# esp32c3phils.net
KiCad netlist of a schematic drawn in Altium Designer
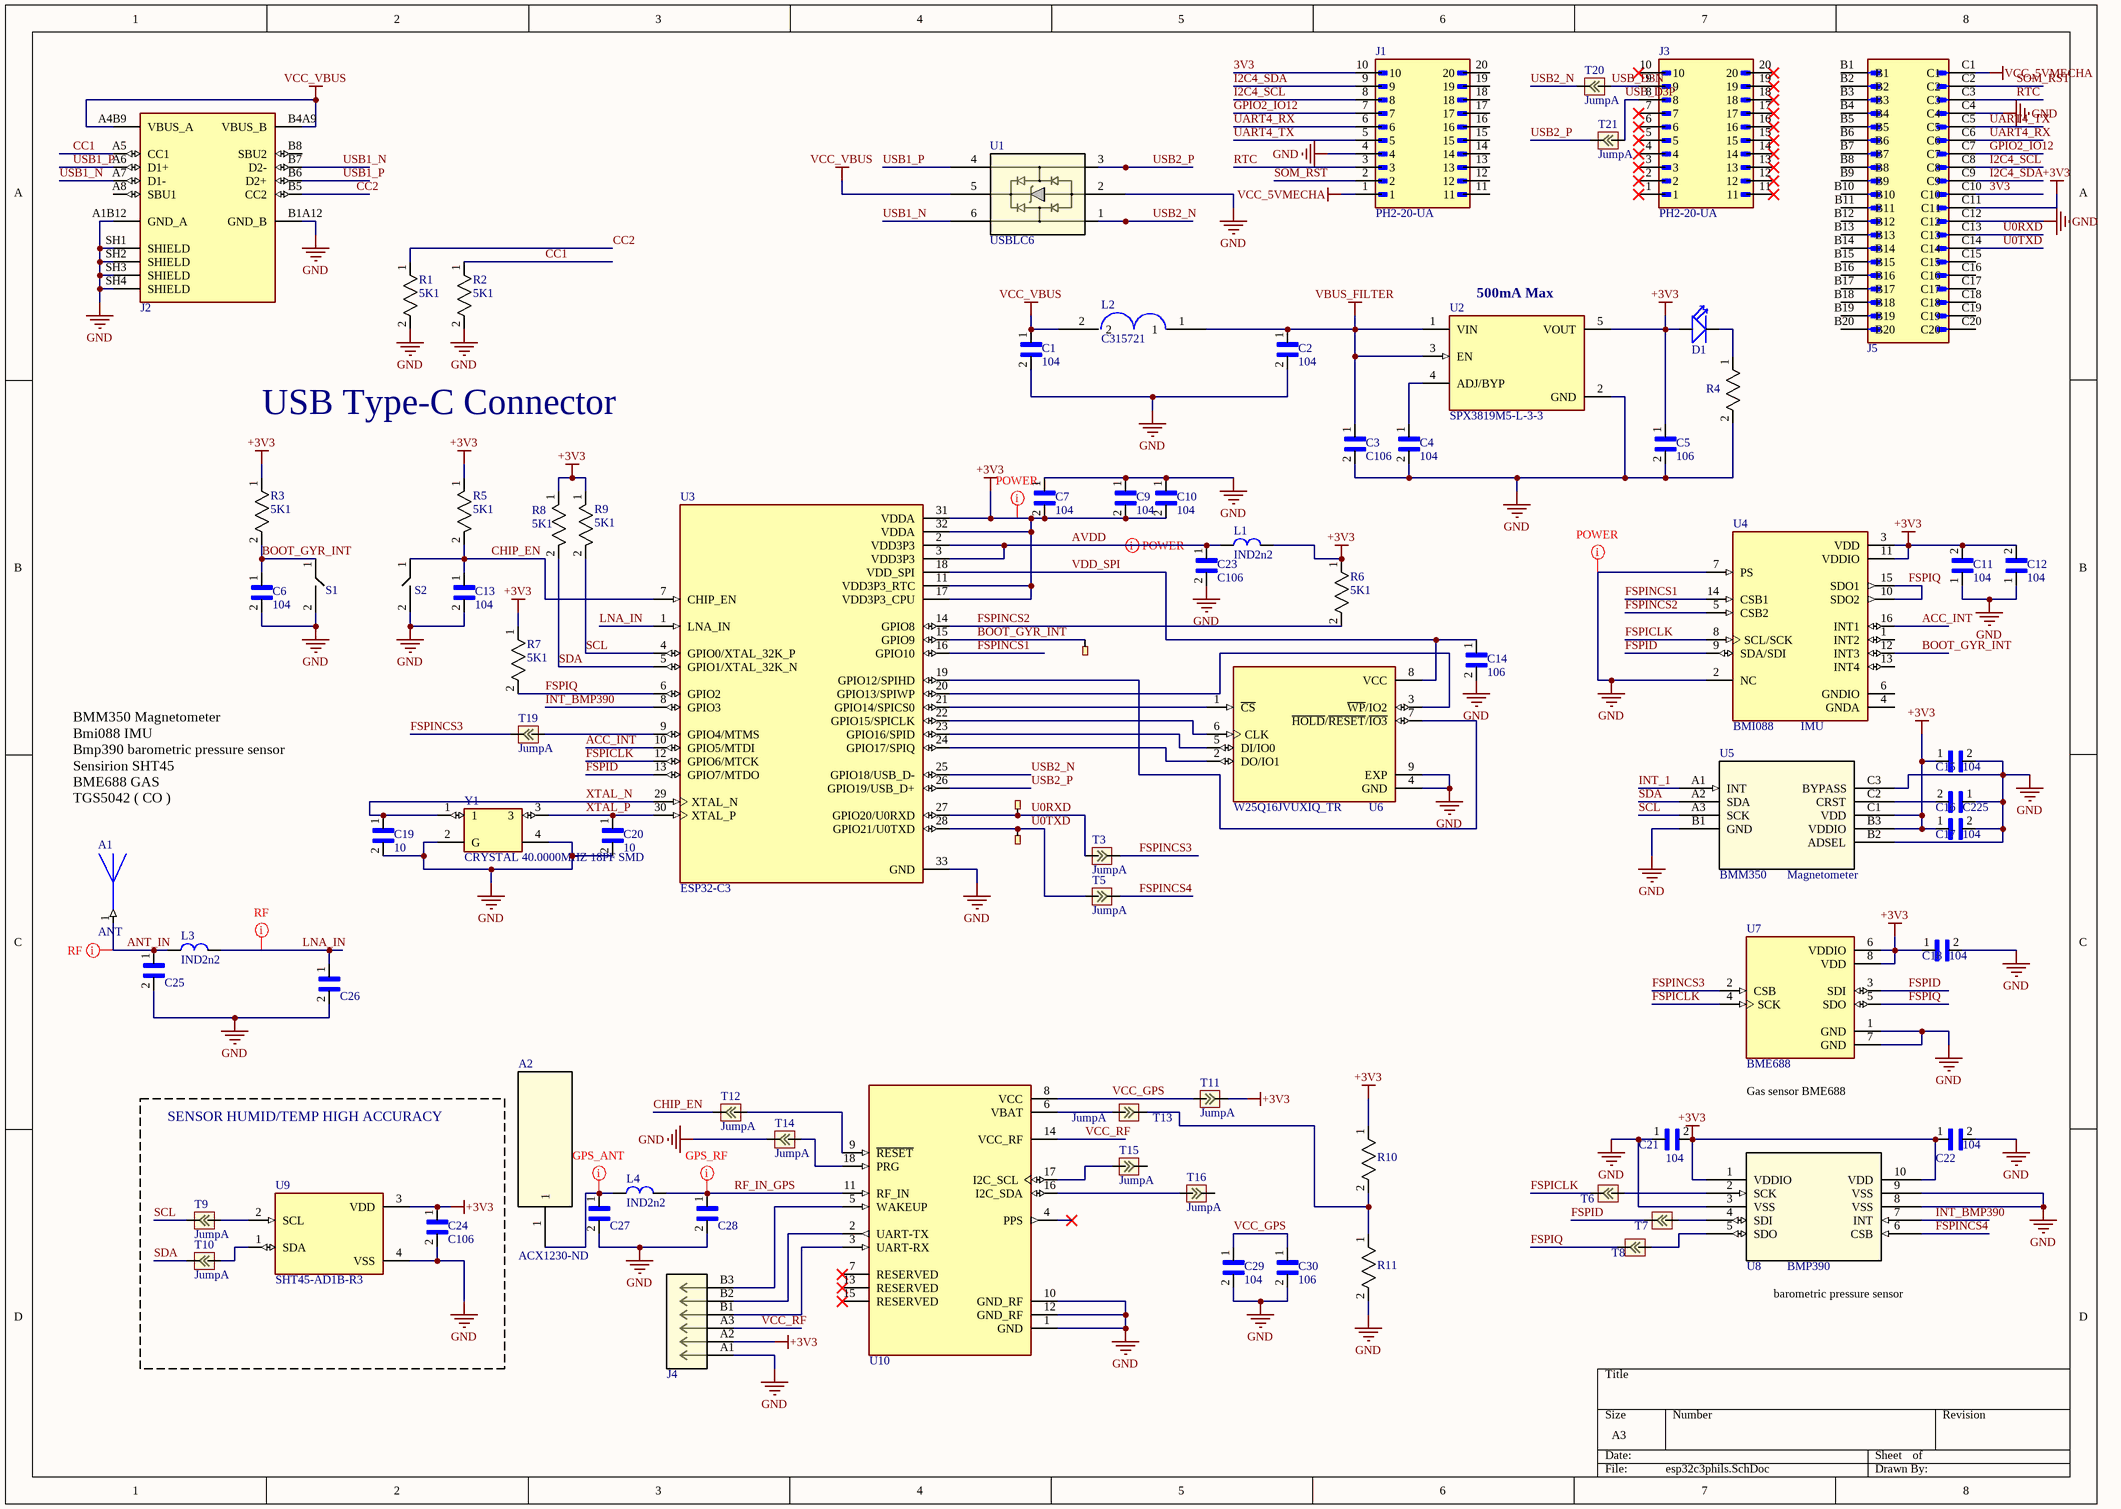
[diagram p0: esp32c3phils.SchDoc]

(export (version "E")
  (design (tool "Eeschema 10.0.6"))
  (components
    (comp (ref "A1")
      (value "ANT")
      (footprint "XDCR_AMCA31-2R450G-S1F-T3")
      (description "Chip Dielectric Antenna; 1dBi; 2450MHz; T/R ¦ Abracon AMCA31-2R450G-S1F-T3")
      (fields (field (name "MANUFACTURER") "Abracon") (field (name "MANUFACTURER PART NUMBER") "C3283994"))
      (libsource (lib "imx8mnano") (part "AMCA31-2R450G-S1F-T3"))
    )
    (comp (ref "A2")
      (value "SMA_VERTICAL")
      (footprint "SMA_VERTICAL")
      (description "connector, rf coaxial, sma str jack for p.c.board, 4 legs, .050 center cont, 50 ohm")
      (fields
        (field (name "MANUFACTURER") "Amphenol Connex")
        (field (name "MANUFACTURER PART NUMBER") "C3174425")
        (field (name "SUPPLIER PART NUMBER 1") "ACX1230-ND")
      )
      (libsource (lib "imx8mnano") (part "SMA_VERTICAL"))
    )
    (comp (ref "C1")
      (value "104")
      (footprint "CAPC1005X55N2")
      (description "Multilayer Ceramic Capacitor, 0.1 uF, 16 V, ï¿½ 10%, X7R, 0402 [1005 Metric]")
      (fields
        (field (name "MANUFACTURER") "Yageo")
        (field (name "MANUFACTURER PART NUMBER") "CC0402KRX7R7BB104")
      )
      (libsource (lib "imx8mnano") (part "CC0402KRX7R7BB104"))
    )
    (comp (ref "C2")
      (value "104")
      (footprint "CAPC1005X55N2")
      (description "Multilayer Ceramic Capacitor, 0.1 uF, 16 V, ï¿½ 10%, X7R, 0402 [1005 Metric]")
      (fields
        (field (name "MANUFACTURER") "Yageo")
        (field (name "MANUFACTURER PART NUMBER") "CC0402KRX7R7BB104")
      )
      (libsource (lib "imx8mnano") (part "CC0402KRX7R7BB104"))
    )
    (comp (ref "C3")
      (value "C106")
      (footprint "RC0402")
      (description "Multilayer Ceramic Chip Capacitor 0402 Size 10uF 10V X5R ±20% Tolerance SMD T/R")
      (fields
        (field (name "MANUFACTURER") "Kyocera AVX")
        (field (name "MANUFACTURER PART NUMBER") "C2167902")
      )
      (libsource (lib "imx8mnano") (part "0402ZD106MAT2A"))
    )
    (comp (ref "C4")
      (value "104")
      (footprint "CAPC1005X55N2")
      (description "Multilayer Ceramic Capacitor, 0.1 uF, 16 V, ï¿½ 10%, X7R, 0402 [1005 Metric]")
      (fields
        (field (name "MANUFACTURER") "Yageo")
        (field (name "MANUFACTURER PART NUMBER") "CC0402KRX7R7BB104")
      )
      (libsource (lib "imx8mnano") (part "CC0402KRX7R7BB104"))
    )
    (comp (ref "C5")
      (value "106")
      (footprint "RC0402")
      (description "Multilayer Ceramic Chip Capacitor 0402 Size 10uF 10V X5R ±20% Tolerance SMD T/R")
      (fields
        (field (name "MANUFACTURER") "Kyocera AVX")
        (field (name "MANUFACTURER PART NUMBER") "C2167902")
      )
      (libsource (lib "imx8mnano") (part "0402ZD106MAT2A"))
    )
    (comp (ref "C6")
      (value "104")
      (footprint "CAPC1005X55N2")
      (description "Multilayer Ceramic Capacitor, 0.1 uF, 16 V, ï¿½ 10%, X7R, 0402 [1005 Metric]")
      (fields
        (field (name "MANUFACTURER") "Yageo")
        (field (name "MANUFACTURER PART NUMBER") "CC0402KRX7R7BB104")
      )
      (libsource (lib "imx8mnano") (part "CC0402KRX7R7BB104"))
    )
    (comp (ref "C7")
      (value "104")
      (footprint "CAPC1005X55N2")
      (description "Multilayer Ceramic Capacitor, 0.1 uF, 16 V, ï¿½ 10%, X7R, 0402 [1005 Metric]")
      (fields
        (field (name "MANUFACTURER") "Yageo")
        (field (name "MANUFACTURER PART NUMBER") "CC0402KRX7R7BB104")
      )
      (libsource (lib "imx8mnano") (part "CC0402KRX7R7BB104"))
    )
    (comp (ref "C9")
      (value "104")
      (footprint "CAPC1005X55N2")
      (description "Multilayer Ceramic Capacitor, 0.1 uF, 16 V, ï¿½ 10%, X7R, 0402 [1005 Metric]")
      (fields
        (field (name "MANUFACTURER") "Yageo")
        (field (name "MANUFACTURER PART NUMBER") "CC0402KRX7R7BB104")
      )
      (libsource (lib "imx8mnano") (part "CC0402KRX7R7BB104"))
    )
    (comp (ref "C10")
      (value "104")
      (footprint "CAPC1005X55N2")
      (description "Multilayer Ceramic Capacitor, 0.1 uF, 16 V, ï¿½ 10%, X7R, 0402 [1005 Metric]")
      (fields
        (field (name "MANUFACTURER") "Yageo")
        (field (name "MANUFACTURER PART NUMBER") "CC0402KRX7R7BB104")
      )
      (libsource (lib "imx8mnano") (part "CC0402KRX7R7BB104"))
    )
    (comp (ref "C11")
      (value "104")
      (footprint "CAPC1005X55N2")
      (description "Multilayer Ceramic Capacitor, 0.1 uF, 16 V, ï¿½ 10%, X7R, 0402 [1005 Metric]")
      (fields
        (field (name "MANUFACTURER") "Yageo")
        (field (name "MANUFACTURER PART NUMBER") "CC0402KRX7R7BB104")
      )
      (libsource (lib "") (part "CC0402KRX7R7BB104_1"))
    )
    (comp (ref "C12")
      (value "104")
      (footprint "CAPC1005X55N2")
      (description "Multilayer Ceramic Capacitor, 0.1 uF, 16 V, ï¿½ 10%, X7R, 0402 [1005 Metric]")
      (fields
        (field (name "MANUFACTURER") "Yageo")
        (field (name "MANUFACTURER PART NUMBER") "CC0402KRX7R7BB104")
      )
      (libsource (lib "") (part "CC0402KRX7R7BB104_1"))
    )
    (comp (ref "C13")
      (value "104")
      (footprint "CAPC1005X55N2")
      (description "Multilayer Ceramic Capacitor, 0.1 uF, 16 V, ï¿½ 10%, X7R, 0402 [1005 Metric]")
      (fields
        (field (name "MANUFACTURER") "Yageo")
        (field (name "MANUFACTURER PART NUMBER") "CC0402KRX7R7BB104")
      )
      (libsource (lib "") (part "CC0402KRX7R7BB104_3"))
    )
    (comp (ref "C14")
      (value "106")
      (footprint "RC0402")
      (description "Multilayer Ceramic Chip Capacitor 0402 Size 10uF 10V X5R ±20% Tolerance SMD T/R")
      (fields
        (field (name "MANUFACTURER") "Kyocera AVX")
        (field (name "MANUFACTURER PART NUMBER") "C2167902")
      )
      (libsource (lib "imx8mnano") (part "0402ZD106MAT2A"))
    )
    (comp (ref "C15")
      (value "104")
      (footprint "CAPC1005X55N2")
      (description "Multilayer Ceramic Capacitor, 0.1 uF, 16 V, ï¿½ 10%, X7R, 0402 [1005 Metric]")
      (fields
        (field (name "MANUFACTURER") "Yageo")
        (field (name "MANUFACTURER PART NUMBER") "CC0402KRX7R7BB104")
      )
      (libsource (lib "") (part "CC0402KRX7R7BB104_2"))
    )
    (comp (ref "C16")
      (value "C225")
      (footprint "RC0402X")
      (description "Multilayer Ceramic Capacitor, 2.2 uF, 6.3 V, ï¿½ 20%, X5R, 0402 [1005 Metric]")
      (fields
        (field (name "MANUFACTURER") "Samsung")
        (field (name "MANUFACTURER PART NUMBER") "CL05A225MQ5NNNC")
      )
      (libsource (lib "imx8mnano") (part "C225"))
    )
    (comp (ref "C17")
      (value "104")
      (footprint "CAPC1005X55N2")
      (description "Multilayer Ceramic Capacitor, 0.1 uF, 16 V, ï¿½ 10%, X7R, 0402 [1005 Metric]")
      (fields
        (field (name "MANUFACTURER") "Yageo")
        (field (name "MANUFACTURER PART NUMBER") "CC0402KRX7R7BB104")
      )
      (libsource (lib "") (part "CC0402KRX7R7BB104_2"))
    )
    (comp (ref "C18")
      (value "104")
      (footprint "CAPC1005X55N2")
      (description "Multilayer Ceramic Capacitor, 0.1 uF, 16 V, ï¿½ 10%, X7R, 0402 [1005 Metric]")
      (fields
        (field (name "MANUFACTURER") "Yageo")
        (field (name "MANUFACTURER PART NUMBER") "CC0402KRX7R7BB104")
      )
      (libsource (lib "") (part "CC0402KRX7R7BB104_2"))
    )
    (comp (ref "C19")
      (value "10")
      (footprint "RC0402")
      (description "0402 10 pF 50 V ±5 % Tolerance NP0 SMT Multilayer Ceramic Capacitor")
      (fields
        (field (name "MANUFACTURER") "Yageo")
        (field (name "MANUFACTURER PART NUMBER") "CC0402JRNPO9BN100")
      )
      (libsource (lib "imx8mnano") (part "C10"))
    )
    (comp (ref "C20")
      (value "10")
      (footprint "RC0402")
      (description "0402 10 pF 50 V ±5 % Tolerance NP0 SMT Multilayer Ceramic Capacitor")
      (fields
        (field (name "MANUFACTURER") "Yageo")
        (field (name "MANUFACTURER PART NUMBER") "CC0402JRNPO9BN100")
      )
      (libsource (lib "imx8mnano") (part "C10"))
    )
    (comp (ref "C21")
      (value "104")
      (footprint "CAPC1005X55N2")
      (description "Multilayer Ceramic Capacitor, 0.1 uF, 16 V, ï¿½ 10%, X7R, 0402 [1005 Metric]")
      (fields
        (field (name "MANUFACTURER") "Yageo")
        (field (name "MANUFACTURER PART NUMBER") "CC0402KRX7R7BB104")
      )
      (libsource (lib "") (part "CC0402KRX7R7BB104_2"))
    )
    (comp (ref "C22")
      (value "104")
      (footprint "CAPC1005X55N2")
      (description "Multilayer Ceramic Capacitor, 0.1 uF, 16 V, ï¿½ 10%, X7R, 0402 [1005 Metric]")
      (fields
        (field (name "MANUFACTURER") "Yageo")
        (field (name "MANUFACTURER PART NUMBER") "CC0402KRX7R7BB104")
      )
      (libsource (lib "") (part "CC0402KRX7R7BB104_2"))
    )
    (comp (ref "C23")
      (value "C106")
      (footprint "RC0402")
      (description "Multilayer Ceramic Chip Capacitor 0402 Size 10uF 10V X5R ±20% Tolerance SMD T/R")
      (fields
        (field (name "MANUFACTURER") "Kyocera AVX")
        (field (name "MANUFACTURER PART NUMBER") "C2167902")
      )
      (libsource (lib "imx8mnano") (part "0402ZD106MAT2A"))
    )
    (comp (ref "C24")
      (value "C106")
      (footprint "RC0402")
      (description "Multilayer Ceramic Chip Capacitor 0402 Size 10uF 10V X5R ±20% Tolerance SMD T/R")
      (fields
        (field (name "MANUFACTURER") "Kyocera AVX")
        (field (name "MANUFACTURER PART NUMBER") "C2167902")
      )
      (libsource (lib "imx8mnano") (part "0402ZD106MAT2A"))
    )
    (comp (ref "C25")
      (value "GJM1555C1H3R3BB01D")
      (footprint "RC0402")
      (description "Multilayer Ceramic Capacitors MLCC - SMD/SMT 0402 3.3pF 50Volts C0G +/-0.1pF")
      (fields (field (name "MANUFACTURER") "Murata") (field (name "MANUFACTURER PART NUMBER") "C76906"))
      (libsource (lib "imx8mnano") (part "3.3PF0402LCSC"))
    )
    (comp (ref "C26")
      (value "GJM1555C1H3R3BB01D")
      (footprint "RC0402")
      (description "Multilayer Ceramic Capacitors MLCC - SMD/SMT 0402 3.3pF 50Volts C0G +/-0.1pF")
      (fields (field (name "MANUFACTURER") "Murata") (field (name "MANUFACTURER PART NUMBER") "C76906"))
      (libsource (lib "imx8mnano") (part "3.3PF0402LCSC"))
    )
    (comp (ref "C27")
      (value "GJM1555C1H3R3BB01D")
      (footprint "RC0402")
      (description "Multilayer Ceramic Capacitors MLCC - SMD/SMT 0402 3.3pF 50Volts C0G +/-0.1pF")
      (fields (field (name "MANUFACTURER") "Murata") (field (name "MANUFACTURER PART NUMBER") "C76906"))
      (libsource (lib "imx8mnano") (part "3.3PF0402LCSC"))
    )
    (comp (ref "C28")
      (value "GJM1555C1H3R3BB01D")
      (footprint "RC0402")
      (description "Multilayer Ceramic Capacitors MLCC - SMD/SMT 0402 3.3pF 50Volts C0G +/-0.1pF")
      (fields (field (name "MANUFACTURER") "Murata") (field (name "MANUFACTURER PART NUMBER") "C76906"))
      (libsource (lib "imx8mnano") (part "3.3PF0402LCSC"))
    )
    (comp (ref "C29")
      (value "104")
      (footprint "CAPC1005X55N2")
      (description "Multilayer Ceramic Capacitor, 0.1 uF, 16 V, ï¿½ 10%, X7R, 0402 [1005 Metric]")
      (fields
        (field (name "MANUFACTURER") "Yageo")
        (field (name "MANUFACTURER PART NUMBER") "CC0402KRX7R7BB104")
      )
      (libsource (lib "imx8mnano") (part "CC0402KRX7R7BB104"))
    )
    (comp (ref "C30")
      (value "106")
      (footprint "RC0402")
      (description "Multilayer Ceramic Chip Capacitor 0402 Size 10uF 10V X5R ±20% Tolerance SMD T/R")
      (fields
        (field (name "MANUFACTURER") "Kyocera AVX")
        (field (name "MANUFACTURER PART NUMBER") "C2167902")
      )
      (libsource (lib "imx8mnano") (part "0402ZD106MAT2A"))
    )
    (comp (ref "D1")
      (value "LED")
      (footprint "LEDM1608X80")
      (description "Single Color LED, Ultra Bright Orange, Water Clear, 1.1mm")
      (fields
        (field (name "MANUFACTURER") "Vishay Lite-On")
        (field (name "MANUFACTURER PART NUMBER") "C157740")
      )
      (libsource (lib "imx8mnano") (part "LTST-C190KFKT"))
    )
    (comp (ref "J1")
      (value "PH2-20-UA")
      (footprint "HEADERPAD_20_80MIL")
      (fields (field (name "MF") "{'manufacturer': u'Adam Tech'}"))
      (libsource (lib "imx8mnano") (part "PH2-20-UA"))
    )
    (comp (ref "J2")
      (value "GSB1C411111DS1HR")
      (footprint "AMPHENOL_GSB1C411111DS1HR")
      (description "USB2.0, Type C, Top mount, Center Height 1.68mm, Single Row Surface Mount")
      (fields (field (name "MANUFACTURER") "Amphenol") (field (name "LCSC PART#") "C3197888"))
      (libsource (lib "imx8mnano") (part "USB-C RECP B"))
    )
    (comp (ref "J3")
      (value "PH2-20-UA")
      (footprint "HEADERPAD_20_80MIL")
      (fields (field (name "MF") "{'manufacturer': u'Adam Tech'}"))
      (libsource (lib "imx8mnano") (part "PH2-20-UA"))
    )
    (comp (ref "J4")
      (value "HEADER6PIN2.54")
      (footprint "HEADER6PIN2.54")
      (description "Conn Unshrouded Header HDR 6 POS 2.54mm Solder ST Top Entry SMD C-Grid Bag")
      (fields (field (name "MANUFACTURER") "Molex") (field (name "MANUFACTURER PART NUMBER") "C780054"))
      (libsource (lib "imx8mnano") (part "HEADER6PIN2.54"))
    )
    (comp (ref "J5")
      (value "HEADER_40PIN_SMD")
      (footprint "AMPHENOL_95157-440LF")
      (description "Conn Unshrouded Header HDR 40 POS 2.54mm Solder ST Top Entry SMD Bulk")
      (fields
        (field (name "MANUFACTURER") "Amphenol ICC / FCI")
        (field (name "MANUFACTURER PART NUMBER") "C6332245")
      )
      (libsource (lib "imx8mnano") (part "HEADER_40PIN_SMD"))
    )
    (comp (ref "L1")
      (value "IND2n2")
      (footprint "INDC1006X60N")
      (description "Inductor with Inductance: 2.2nH Tol. +/-0.1nH, Package: 0402 (1005)")
      (fields (field (name "MF") "Murata Electronics") (field (name "MP") "LQW15AN2N2B80D"))
      (libsource (lib "imx8mnano") (part "IND2n2"))
    )
    (comp (ref "L2")
      (value "C315721")
      (footprint "IND-SMD_L2.5-W2.0_SWPA252012S")
      (description "Fixed Ind 2.220%UH 0.114 Ohm 1800")
      (fields (field (name "MANUFACTURER") "Sunlord"))
      (libsource (lib "imx8mnano") (part "SPH252010H2R2MT"))
    )
    (comp (ref "L3")
      (value "IND2n2")
      (footprint "INDC1006X60N")
      (description "Inductor with Inductance: 2.2nH Tol. +/-0.1nH, Package: 0402 (1005)")
      (fields (field (name "MF") "Murata Electronics") (field (name "MP") "LQW15AN2N2B80D"))
      (libsource (lib "imx8mnano") (part "IND2n2"))
    )
    (comp (ref "L4")
      (value "IND2n2")
      (footprint "INDC1006X60N")
      (description "Inductor with Inductance: 2.2nH Tol. +/-0.1nH, Package: 0402 (1005)")
      (fields (field (name "MF") "Murata Electronics") (field (name "MP") "LQW15AN2N2B80D"))
      (libsource (lib "imx8mnano") (part "IND2n2"))
    )
    (comp (ref "R1")
      (value "5K1")
      (footprint "RC0402")
      (description "SMD Chip Resistor, 5.1 kOhm, ï¿½ 1%, 62.5 mW, 0402 [1005 Metric], Thick Film, General Purpose")
      (fields (field (name "MANUFACTURER") "Yageo") (field (name "MANUFACTURER PART NUMBER") "C105872"))
      (libsource (lib "imx8mnano") (part "RC0402FR-075K1L"))
    )
    (comp (ref "R2")
      (value "5K1")
      (footprint "RC0402")
      (description "SMD Chip Resistor, 5.1 kOhm, ï¿½ 1%, 62.5 mW, 0402 [1005 Metric], Thick Film, General Purpose")
      (fields (field (name "MANUFACTURER") "Yageo") (field (name "MANUFACTURER PART NUMBER") "C105872"))
      (libsource (lib "imx8mnano") (part "RC0402FR-075K1L"))
    )
    (comp (ref "R3")
      (value "5K1")
      (footprint "RC0402")
      (description "SMD Chip Resistor, 5.1 kOhm, ï¿½ 1%, 62.5 mW, 0402 [1005 Metric], Thick Film, General Purpose")
      (fields (field (name "MANUFACTURER") "Yageo") (field (name "MANUFACTURER PART NUMBER") "C105872"))
      (libsource (lib "imx8mnano") (part "RC0402FR-075K1L"))
    )
    (comp (ref "R4")
      (value "ERA-2AEB202X")
      (footprint "RC0402X")
      (description "Res Thin Film 0402 2K Ohm 0.1% 0.063W ±25ppm/°C Molded SMD Punched Carrier T/R")
      (fields
        (field (name "MANUFACTURER") "Panasonic")
        (field (name "MANUFACTURER PART NUMBER") "ERA2AEB202X")
      )
      (libsource (lib "imx8mnano") (part "2K2"))
    )
    (comp (ref "R5")
      (value "5K1")
      (footprint "RC0402")
      (description "SMD Chip Resistor, 5.1 kOhm, ï¿½ 1%, 62.5 mW, 0402 [1005 Metric], Thick Film, General Purpose")
      (fields (field (name "MANUFACTURER") "Yageo") (field (name "MANUFACTURER PART NUMBER") "C105872"))
      (libsource (lib "imx8mnano") (part "RC0402FR-075K1L"))
    )
    (comp (ref "R6")
      (value "5K1")
      (footprint "RC0402")
      (description "SMD Chip Resistor, 5.1 kOhm, ï¿½ 1%, 62.5 mW, 0402 [1005 Metric], Thick Film, General Purpose")
      (fields (field (name "MANUFACTURER") "Yageo") (field (name "MANUFACTURER PART NUMBER") "C105872"))
      (libsource (lib "imx8mnano") (part "RC0402FR-075K1L"))
    )
    (comp (ref "R7")
      (value "5K1")
      (footprint "RC0402")
      (description "SMD Chip Resistor, 5.1 kOhm, ï¿½ 1%, 62.5 mW, 0402 [1005 Metric], Thick Film, General Purpose")
      (fields (field (name "MANUFACTURER") "Yageo") (field (name "MANUFACTURER PART NUMBER") "C105872"))
      (libsource (lib "imx8mnano") (part "RC0402FR-075K1L"))
    )
    (comp (ref "R8")
      (value "5K1")
      (footprint "RC0402")
      (description "SMD Chip Resistor, 5.1 kOhm, ï¿½ 1%, 62.5 mW, 0402 [1005 Metric], Thick Film, General Purpose")
      (fields (field (name "MANUFACTURER") "Yageo") (field (name "MANUFACTURER PART NUMBER") "C105872"))
      (libsource (lib "imx8mnano") (part "RC0402FR-075K1L"))
    )
    (comp (ref "R9")
      (value "5K1")
      (footprint "RC0402")
      (description "SMD Chip Resistor, 5.1 kOhm, ï¿½ 1%, 62.5 mW, 0402 [1005 Metric], Thick Film, General Purpose")
      (fields (field (name "MANUFACTURER") "Yageo") (field (name "MANUFACTURER PART NUMBER") "C105872"))
      (libsource (lib "imx8mnano") (part "RC0402FR-075K1L"))
    )
    (comp (ref "R10")
      (value "15K0402")
      (footprint "RC0402X")
      (description "Res Thin Film 0402 15K Ohm 0.1% 0.063W(1/16W) ±25ppm/C Pad SMD T/R")
      (fields (field (name "MANUFACTURER") "Yageo") (field (name "MANUFACTURER PART NUMBER") "C852545"))
      (libsource (lib "imx8mnano") (part "15K0402"))
    )
    (comp (ref "R11")
      (value "33K0402")
      (footprint "RC0402X")
      (description "SMD Chip Resistor, 33 Kohm, ½ 5%, 62.5 Mw, 0402 [1005 Metric], Thick Film, General Purpose")
      (fields (field (name "MANUFACTURER") "Yageo") (field (name "MANUFACTURER PART NUMBER") "C138003"))
      (libsource (lib "imx8mnano") (part "33K0402"))
    )
    (comp (ref "S1")
      (value "SW_P")
      (footprint "SW")
      (description "Switch Tactile N.O. SPST Round Button Gull Wing 0.05A 12VDC 0.98N SMD T/R")
      (fields
        (field (name "MANUFACTURER") "Alps Electric")
        (field (name "MANUFACTURER PART NUMBER") "C202388")
      )
      (libsource (lib "imx8mnano") (part "SW_P"))
    )
    (comp (ref "S2")
      (value "SW_P")
      (footprint "SW")
      (description "Switch Tactile N.O. SPST Round Button Gull Wing 0.05A 12VDC 0.98N SMD T/R")
      (fields
        (field (name "MANUFACTURER") "Alps Electric")
        (field (name "MANUFACTURER PART NUMBER") "C202388")
      )
      (libsource (lib "imx8mnano") (part "SW_P"))
    )
    (comp (ref "T1") (value "TP") (footprint "TP") (libsource (lib "") (part "TP_1")))
    (comp (ref "T2") (value "TP") (footprint "TP") (libsource (lib "imx8mnano") (part "TP")))
    (comp (ref "T3") (value "JumpA") (footprint "JumpA") (libsource (lib "") (part "JumpA_1")))
    (comp (ref "T4") (value "TP") (footprint "TP") (libsource (lib "") (part "TP_1")))
    (comp (ref "T5") (value "JumpA") (footprint "JumpA") (libsource (lib "") (part "JumpA_1")))
    (comp (ref "T6") (value "JumpA") (footprint "JumpA") (libsource (lib "imx8mnano") (part "JumpA")))
    (comp (ref "T7") (value "JumpA") (footprint "JumpA") (libsource (lib "imx8mnano") (part "JumpA")))
    (comp (ref "T8") (value "JumpA") (footprint "JumpA") (libsource (lib "imx8mnano") (part "JumpA")))
    (comp (ref "T9") (value "JumpA") (footprint "JumpA") (libsource (lib "imx8mnano") (part "JumpA")))
    (comp (ref "T10") (value "JumpA") (footprint "JumpA") (libsource (lib "imx8mnano") (part "JumpA")))
    (comp (ref "T11") (value "JumpA") (footprint "JumpA") (libsource (lib "") (part "JumpA_1")))
    (comp (ref "T12") (value "JumpA") (footprint "JumpA") (libsource (lib "imx8mnano") (part "JumpA")))
    (comp (ref "T13") (value "JumpA") (footprint "JumpA") (libsource (lib "") (part "JumpA_1")))
    (comp (ref "T14") (value "JumpA") (footprint "JumpA") (libsource (lib "imx8mnano") (part "JumpA")))
    (comp (ref "T15") (value "JumpA") (footprint "JumpA") (libsource (lib "") (part "JumpA_1")))
    (comp (ref "T16") (value "JumpA") (footprint "JumpA") (libsource (lib "") (part "JumpA_1")))
    (comp (ref "T19") (value "JumpA") (footprint "JumpA") (libsource (lib "imx8mnano") (part "JumpA")))
    (comp (ref "T20") (value "JumpA") (footprint "JumpA") (libsource (lib "imx8mnano") (part "JumpA")))
    (comp (ref "T21") (value "JumpA") (footprint "JumpA") (libsource (lib "imx8mnano") (part "JumpA")))
    (comp (ref "U1")
      (value "USBLC6")
      (footprint "SOT23-6L_STM")
      (description "ESD Suppressor Diode Array Dual Uni-Dir 15kV Air Gap/15kV Contact Disc 6-Pin SOT-23 T/R")
      (fields
        (field (name "MANUFACTURER") "STMicroelectronics")
        (field (name "MANUFACTURER PART NUMBER") "C7519")
      )
      (libsource (lib "imx8mnano") (part "USBLC6-2SC6"))
    )
    (comp (ref "U2")
      (value "SPX3819M5-L-3-3")
      (footprint "SOT95P280X145-5N")
      (description "Linear Voltage Regulator IC Positive Fixed 1 Output 500mA SOT-23-5")
      (fields (field (name "MF") "MaxLinear, Inc.") (field (name "MP") "SPX3819M5-L-3-3/TR"))
      (libsource (lib "imx8mnano") (part "SPX3819M5-L-3-3"))
    )
    (comp (ref "U3")
      (value "ESP32-C3")
      (footprint "QFN50P500X500X90-33N")
      (fields (field (name "MF") "Espressif Systems") (field (name "MANUFACTURER PART NUMBER") "C2838500"))
      (libsource (lib "imx8mnano") (part "ESP32-C3"))
    )
    (comp (ref "U4")
      (value "BMI088")
      (footprint "PQFN50P450X300X100-16N")
      (fields (field (name "MANUFACTURER PART NUMBER") "C194919"))
      (libsource (lib "imx8mnano") (part "BMI088"))
    )
    (comp (ref "U5")
      (value "BMM350")
      (footprint "BGA9_BMM350_BOS")
      (description "No Description Available")
      (fields (field (name "MANUFACTURER PART NUMBER") "C17225907"))
      (libsource (lib "imx8mnano") (part "BMM350"))
    )
    (comp (ref "U6")
      (value "W25Q16JVUXIQ_TR")
      (footprint "IC_W25Q16JVUXIQ_TR")
      (description "NOR Flash Serial (SPI, Dual SPI, Quad SPI) 3V/3.3V 16M-bit 2M x 8 6ns 8-Pin USON EP T/R")
      (fields (field (name "MF") "Winbond") (field (name "MP") "W25Q16JVUXIQ TR"))
      (libsource (lib "imx8mnano") (part "W25Q16JVUXIQ_TR"))
    )
    (comp (ref "U7")
      (value "BME688")
      (footprint "IC_BME688")
      (description "Gas sensor measuring relative humidity, barometric pressure, ambient temperature and gas (VOC)")
      (fields (field (name "MANUFACTURER PART NUMBER") "C3664478"))
      (libsource (lib "imx8mnano") (part "BME688"))
    )
    (comp (ref "U8")
      (value "BMP390")
      (footprint "10LGA_2X2X0p75_BOS")
      (description "No Description Available")
      (fields (field (name "MANUFACTURER PART NUMBER") "C2684802"))
      (libsource (lib "imx8mnano") (part "BMP390"))
    )
    (comp (ref "U9")
      (value "SHT45-AD1B-R3")
      (footprint "SHT4X")
      (fields (field (name "MF") "Sensirion"))
      (libsource (lib "imx8mnano") (part "SHT45-AD1B-R3"))
    )
    (comp (ref "U10")
      (value "TESEO-LIV4FTR")
      (footprint "XCVR_TESEO-LIV4FTR")
      (description "GNSS Module Dual-Band 3V to 3.63V 18-Pin LCC T/R")
      (fields
        (field (name "MANUFACTURER") "STMicroelectronics")
        (field (name "MANUFACTURER PART NUMBER") "C6284698")
      )
      (libsource (lib "imx8mnano") (part "TESEO-LIV4FTR"))
    )
    (comp (ref "Y1")
      (value "CRYSTAL 40.0000MHZ 18PF SMD")
      (footprint "XTAL_ECS-400-18-33-JGN-TR3")
      (fields
        (field (name "MP") "ECS-400-18-33-JGN-TR3")
        (field (name "MF") "{'manufacturer': u'ECS Inc.'}")
        (field (name "MANUFACTURER PART NUMBER") "C5765977")
      )
      (libsource (lib "imx8mnano") (part "ECS-400-18-33-JGN-TR3"))
    )
  )
  (nets
    (net (code "1") (name "+3V3") (class "Default")
      (node (ref "C10") (pin "2") (pinfunction "2_2") (pintype "passive"))
      (node (ref "C11") (pin "2") (pinfunction "2_2") (pintype "passive"))
      (node (ref "C12") (pin "2") (pinfunction "2_2") (pintype "passive"))
      (node (ref "C15") (pin "1") (pinfunction "1_1") (pintype "passive"))
      (node (ref "C17") (pin "1") (pinfunction "1_1") (pintype "passive"))
      (node (ref "C18") (pin "1") (pinfunction "1_1") (pintype "passive"))
      (node (ref "C21") (pin "2") (pinfunction "2_2") (pintype "passive"))
      (node (ref "C22") (pin "1") (pinfunction "1_1") (pintype "passive"))
      (node (ref "C24") (pin "1") (pinfunction "1_1") (pintype "passive"))
      (node (ref "C5") (pin "1") (pinfunction "1_1") (pintype "passive"))
      (node (ref "C7") (pin "2") (pinfunction "2_2") (pintype "passive"))
      (node (ref "C9") (pin "2") (pinfunction "2_2") (pintype "passive"))
      (node (ref "D1") (pin "A") (pinfunction "A_A") (pintype "passive"))
      (node (ref "J4") (pin "A2") (pinfunction "A2_A2") (pintype "passive"))
      (node (ref "J5") (pin "C11") (pinfunction "C11_C11") (pintype "passive"))
      (node (ref "L1") (pin "2") (pinfunction "2_2") (pintype "passive"))
      (node (ref "R10") (pin "1") (pinfunction "1_1") (pintype "passive"))
      (node (ref "R3") (pin "1") (pinfunction "1_1") (pintype "passive"))
      (node (ref "R5") (pin "1") (pinfunction "1_1") (pintype "passive"))
      (node (ref "R6") (pin "1") (pinfunction "1_1") (pintype "passive"))
      (node (ref "R7") (pin "1") (pinfunction "1_1") (pintype "passive"))
      (node (ref "R8") (pin "1") (pinfunction "1_1") (pintype "passive"))
      (node (ref "R9") (pin "1") (pinfunction "1_1") (pintype "passive"))
      (node (ref "T11") (pin "2") (pinfunction "2_2") (pintype "passive"))
      (node (ref "U2") (pin "5") (pinfunction "VOUT_5") (pintype "passive"))
      (node (ref "U3") (pin "11") (pinfunction "VDD3P3_RTC_11") (pintype "power_in"))
      (node (ref "U3") (pin "17") (pinfunction "VDD3P3_CPU_17") (pintype "power_in"))
      (node (ref "U3") (pin "31") (pinfunction "VDDA_31") (pintype "power_in"))
      (node (ref "U3") (pin "32") (pinfunction "VDDA_32") (pintype "power_in"))
      (node (ref "U4") (pin "11") (pinfunction "VDDIO_11") (pintype "power_in"))
      (node (ref "U4") (pin "3") (pinfunction "VDD_3") (pintype "power_in"))
      (node (ref "U5") (pin "B3") (pinfunction "VDDIO_B3") (pintype "power_in"))
      (node (ref "U5") (pin "C1") (pinfunction "VDD_C1") (pintype "power_in"))
      (node (ref "U7") (pin "6") (pinfunction "VDDIO_6") (pintype "power_in"))
      (node (ref "U7") (pin "8") (pinfunction "VDD_8") (pintype "power_in"))
      (node (ref "U8") (pin "1") (pinfunction "VDDIO_1") (pintype "power_in"))
      (node (ref "U8") (pin "10") (pinfunction "VDD_10") (pintype "power_in"))
      (node (ref "U9") (pin "3") (pinfunction "VDD_3") (pintype "power_in"))
    )
    (net (code "2") (name "/3V3") (class "Default")
      (node (ref "J1") (pin "10") (pinfunction "10_10") (pintype "passive"))
      (node (ref "J5") (pin "C10") (pinfunction "C10_C10") (pintype "passive"))
    )
    (net (code "3") (name "/ACC_INT") (class "Default")
      (node (ref "U3") (pin "10") (pinfunction "GPIO5/MTDI_10") (pintype "bidirectional"))
      (node (ref "U4") (pin "16") (pinfunction "INT1_16") (pintype "bidirectional"))
    )
    (net (code "4") (name "/ANT_IN") (class "Default")
      (node (ref "A1") (pin "1") (pinfunction "1_1") (pintype "input"))
      (node (ref "C25") (pin "1") (pinfunction "1_1") (pintype "passive"))
      (node (ref "L3") (pin "1") (pinfunction "1_1") (pintype "passive"))
    )
    (net (code "5") (name "/AVDD") (class "Default")
      (node (ref "C23") (pin "1") (pinfunction "1_1") (pintype "passive"))
      (node (ref "L1") (pin "1") (pinfunction "1_1") (pintype "passive"))
      (node (ref "U3") (pin "2") (pinfunction "VDD3P3_2") (pintype "power_in"))
      (node (ref "U3") (pin "3") (pinfunction "VDD3P3_3") (pintype "power_in"))
    )
    (net (code "6") (name "/BOOT_GYR_INT") (class "Default")
      (node (ref "C6") (pin "1") (pinfunction "1_1") (pintype "passive"))
      (node (ref "R3") (pin "2") (pinfunction "2_2") (pintype "passive"))
      (node (ref "S1") (pin "1") (pinfunction "1_1") (pintype "passive"))
      (node (ref "T1") (pin "1") (pinfunction "1_1") (pintype "passive"))
      (node (ref "U3") (pin "15") (pinfunction "GPIO9_15") (pintype "bidirectional"))
      (node (ref "U4") (pin "12") (pinfunction "INT3_12") (pintype "bidirectional"))
    )
    (net (code "7") (name "/CC1") (class "Default")
      (node (ref "J2") (pin "A5") (pinfunction "CC1_A5") (pintype "bidirectional"))
      (node (ref "R2") (pin "1") (pinfunction "1_1") (pintype "passive"))
    )
    (net (code "8") (name "/CC2") (class "Default")
      (node (ref "J2") (pin "B5") (pinfunction "CC2_B5") (pintype "bidirectional"))
      (node (ref "R1") (pin "1") (pinfunction "1_1") (pintype "passive"))
    )
    (net (code "9") (name "/CHIP_EN") (class "Default")
      (node (ref "C13") (pin "1") (pinfunction "1_1") (pintype "passive"))
      (node (ref "R5") (pin "2") (pinfunction "2_2") (pintype "passive"))
      (node (ref "S2") (pin "1") (pinfunction "1_1") (pintype "passive"))
      (node (ref "T12") (pin "2") (pinfunction "2_2") (pintype "passive"))
      (node (ref "U3") (pin "7") (pinfunction "CHIP_EN_7") (pintype "input"))
    )
    (net (code "10") (name "/FSPICLK") (class "Default")
      (node (ref "T6") (pin "2") (pinfunction "2_2") (pintype "passive"))
      (node (ref "U3") (pin "12") (pinfunction "GPIO6/MTCK_12") (pintype "bidirectional"))
      (node (ref "U4") (pin "8") (pinfunction "SCL/SCK_8") (pintype "input"))
      (node (ref "U7") (pin "4") (pinfunction "SCK_4") (pintype "input"))
    )
    (net (code "11") (name "/FSPID") (class "Default")
      (node (ref "T7") (pin "2") (pinfunction "2_2") (pintype "passive"))
      (node (ref "U3") (pin "13") (pinfunction "GPIO7/MTDO_13") (pintype "bidirectional"))
      (node (ref "U4") (pin "9") (pinfunction "SDA/SDI_9") (pintype "bidirectional"))
      (node (ref "U7") (pin "3") (pinfunction "SDI_3") (pintype "bidirectional"))
    )
    (net (code "12") (name "/FSPINCS1") (class "Default")
      (node (ref "U3") (pin "16") (pinfunction "GPIO10_16") (pintype "bidirectional"))
      (node (ref "U4") (pin "14") (pinfunction "CSB1_14") (pintype "input"))
    )
    (net (code "13") (name "/FSPINCS2") (class "Default")
      (node (ref "R6") (pin "2") (pinfunction "2_2") (pintype "passive"))
      (node (ref "U3") (pin "14") (pinfunction "GPIO8_14") (pintype "bidirectional"))
      (node (ref "U4") (pin "5") (pinfunction "CSB2_5") (pintype "input"))
    )
    (net (code "14") (name "/FSPINCS3") (class "Default")
      (node (ref "T19") (pin "2") (pinfunction "2_2") (pintype "passive"))
      (node (ref "T3") (pin "2") (pinfunction "2_2") (pintype "passive"))
      (node (ref "U7") (pin "2") (pinfunction "CSB_2") (pintype "input"))
    )
    (net (code "15") (name "/FSPINCS4") (class "Default")
      (node (ref "T5") (pin "2") (pinfunction "2_2") (pintype "passive"))
      (node (ref "U8") (pin "6") (pinfunction "CSB_6") (pintype "input"))
    )
    (net (code "16") (name "/FSPIQ") (class "Default")
      (node (ref "R7") (pin "2") (pinfunction "2_2") (pintype "passive"))
      (node (ref "T8") (pin "2") (pinfunction "2_2") (pintype "passive"))
      (node (ref "U3") (pin "6") (pinfunction "GPIO2_6") (pintype "bidirectional"))
      (node (ref "U4") (pin "10") (pinfunction "SDO2_10") (pintype "output"))
      (node (ref "U4") (pin "15") (pinfunction "SDO1_15") (pintype "output"))
      (node (ref "U7") (pin "5") (pinfunction "SDO_5") (pintype "bidirectional"))
    )
    (net (code "17") (name "/GPIO2_IO12") (class "Default")
      (node (ref "J1") (pin "7") (pinfunction "7_7") (pintype "passive"))
      (node (ref "J5") (pin "C7") (pinfunction "C7_C7") (pintype "passive"))
    )
    (net (code "18") (name "/I2C4_SCL") (class "Default")
      (node (ref "J1") (pin "8") (pinfunction "8_8") (pintype "passive"))
      (node (ref "J5") (pin "C8") (pinfunction "C8_C8") (pintype "passive"))
    )
    (net (code "19") (name "/I2C4_SDA") (class "Default")
      (node (ref "J1") (pin "9") (pinfunction "9_9") (pintype "passive"))
      (node (ref "J5") (pin "C9") (pinfunction "C9_C9") (pintype "passive"))
    )
    (net (code "20") (name "/INT_1") (class "Default")
      (node (ref "U5") (pin "A1") (pinfunction "INT_A1") (pintype "input"))
    )
    (net (code "21") (name "/INT_BMP390") (class "Default")
      (node (ref "U3") (pin "8") (pinfunction "GPIO3_8") (pintype "bidirectional"))
      (node (ref "U8") (pin "7") (pinfunction "INT_7") (pintype "input"))
    )
    (net (code "22") (name "/LNA_IN") (class "Default")
      (node (ref "C26") (pin "1") (pinfunction "1_1") (pintype "passive"))
      (node (ref "L3") (pin "2") (pinfunction "2_2") (pintype "passive"))
      (node (ref "U3") (pin "1") (pinfunction "LNA_IN_1") (pintype "input"))
    )
    (net (code "23") (name "/RF_IN_GPS") (class "Default")
      (node (ref "C28") (pin "1") (pinfunction "1_1") (pintype "passive"))
      (node (ref "L4") (pin "2") (pinfunction "2_2") (pintype "passive"))
      (node (ref "U10") (pin "11") (pinfunction "RF_IN_11") (pintype "input"))
    )
    (net (code "24") (name "/RTC") (class "Default")
      (node (ref "J1") (pin "3") (pinfunction "3_3") (pintype "passive"))
      (node (ref "J5") (pin "C3") (pinfunction "C3_C3") (pintype "passive"))
    )
    (net (code "25") (name "/SCL") (class "Default")
      (node (ref "R9") (pin "2") (pinfunction "2_2") (pintype "passive"))
      (node (ref "T9") (pin "2") (pinfunction "2_2") (pintype "passive"))
      (node (ref "U3") (pin "4") (pinfunction "GPIO0/XTAL_32K_P_4") (pintype "bidirectional"))
      (node (ref "U5") (pin "A3") (pinfunction "SCK_A3") (pintype "passive"))
    )
    (net (code "26") (name "/SDA") (class "Default")
      (node (ref "R8") (pin "2") (pinfunction "2_2") (pintype "passive"))
      (node (ref "T10") (pin "2") (pinfunction "2_2") (pintype "passive"))
      (node (ref "U3") (pin "5") (pinfunction "GPIO1/XTAL_32K_N_5") (pintype "bidirectional"))
      (node (ref "U5") (pin "A2") (pinfunction "SDA_A2") (pintype "passive"))
    )
    (net (code "27") (name "/SOM_RST") (class "Default")
      (node (ref "J1") (pin "2") (pinfunction "2_2") (pintype "passive"))
      (node (ref "J5") (pin "C2") (pinfunction "C2_C2") (pintype "passive"))
    )
    (net (code "28") (name "/U0RXD") (class "Default")
      (node (ref "J5") (pin "C13") (pinfunction "C13_C13") (pintype "passive"))
      (node (ref "T2") (pin "1") (pinfunction "1_1") (pintype "passive"))
      (node (ref "T3") (pin "1") (pinfunction "1_1") (pintype "passive"))
      (node (ref "U3") (pin "27") (pinfunction "GPIO20/U0RXD_27") (pintype "bidirectional"))
    )
    (net (code "29") (name "/U0TXD") (class "Default")
      (node (ref "J5") (pin "C14") (pinfunction "C14_C14") (pintype "passive"))
      (node (ref "T4") (pin "1") (pinfunction "1_1") (pintype "passive"))
      (node (ref "T5") (pin "1") (pinfunction "1_1") (pintype "passive"))
      (node (ref "U3") (pin "28") (pinfunction "GPIO21/U0TXD_28") (pintype "bidirectional"))
    )
    (net (code "30") (name "/UART4_RX") (class "Default")
      (node (ref "J1") (pin "6") (pinfunction "6_6") (pintype "passive"))
      (node (ref "J5") (pin "C6") (pinfunction "C6_C6") (pintype "passive"))
    )
    (net (code "31") (name "/UART4_TX") (class "Default")
      (node (ref "J1") (pin "5") (pinfunction "5_5") (pintype "passive"))
      (node (ref "J5") (pin "C5") (pinfunction "C5_C5") (pintype "passive"))
    )
    (net (code "32") (name "/USB1_N") (class "Default")
      (node (ref "J2") (pin "A7") (pinfunction "D1-_A7") (pintype "bidirectional"))
      (node (ref "J2") (pin "B7") (pinfunction "D2-_B7") (pintype "bidirectional"))
      (node (ref "U1") (pin "6") (pinfunction "6_6") (pintype "passive"))
    )
    (net (code "33") (name "/USB1_P") (class "Default")
      (node (ref "J2") (pin "A6") (pinfunction "D1+_A6") (pintype "bidirectional"))
      (node (ref "J2") (pin "B6") (pinfunction "D2+_B6") (pintype "bidirectional"))
      (node (ref "U1") (pin "4") (pinfunction "4_4") (pintype "passive"))
    )
    (net (code "34") (name "/USB2_N") (class "Default")
      (node (ref "T20") (pin "2") (pinfunction "2_2") (pintype "passive"))
      (node (ref "U1") (pin "1") (pinfunction "1_1") (pintype "passive"))
      (node (ref "U3") (pin "25") (pinfunction "GPIO18/USB_D-_25") (pintype "bidirectional"))
    )
    (net (code "35") (name "/USB2_P") (class "Default")
      (node (ref "T21") (pin "2") (pinfunction "2_2") (pintype "passive"))
      (node (ref "U1") (pin "3") (pinfunction "3_3") (pintype "passive"))
      (node (ref "U3") (pin "26") (pinfunction "GPIO19/USB_D+_26") (pintype "bidirectional"))
    )
    (net (code "36") (name "/USB_D3N") (class "Default")
      (node (ref "J3") (pin "9") (pinfunction "9_9") (pintype "passive"))
      (node (ref "T20") (pin "1") (pinfunction "1_1") (pintype "passive"))
    )
    (net (code "37") (name "/USB_D3P") (class "Default")
      (node (ref "J3") (pin "8") (pinfunction "8_8") (pintype "passive"))
      (node (ref "T21") (pin "1") (pinfunction "1_1") (pintype "passive"))
    )
    (net (code "38") (name "/VCC_GPS") (class "Default")
      (node (ref "C29") (pin "1") (pinfunction "1_1") (pintype "passive"))
      (node (ref "C30") (pin "1") (pinfunction "1_1") (pintype "passive"))
      (node (ref "T11") (pin "1") (pinfunction "1_1") (pintype "passive"))
      (node (ref "U10") (pin "8") (pinfunction "VCC_8") (pintype "power_in"))
    )
    (net (code "39") (name "/VCC_RF") (class "Default")
      (node (ref "J4") (pin "A3") (pinfunction "A3_A3") (pintype "passive"))
      (node (ref "U10") (pin "14") (pinfunction "VCC_RF_14") (pintype "power_in"))
    )
    (net (code "40") (name "/VDD_SPI") (class "Default")
      (node (ref "C14") (pin "1") (pinfunction "1_1") (pintype "passive"))
      (node (ref "U3") (pin "18") (pinfunction "VDD_SPI_18") (pintype "power_in"))
      (node (ref "U6") (pin "8") (pinfunction "VCC_8") (pintype "power_in"))
    )
    (net (code "41") (name "/XTAL_N") (class "Default")
      (node (ref "C19") (pin "1") (pinfunction "1_1") (pintype "passive"))
      (node (ref "U3") (pin "29") (pinfunction "XTAL_N_29") (pintype "input"))
      (node (ref "Y1") (pin "1") (pinfunction "1_1") (pintype "bidirectional"))
    )
    (net (code "42") (name "/XTAL_P") (class "Default")
      (node (ref "C20") (pin "1") (pinfunction "1_1") (pintype "passive"))
      (node (ref "U3") (pin "30") (pinfunction "XTAL_P_30") (pintype "input"))
      (node (ref "Y1") (pin "3") (pinfunction "3_3") (pintype "bidirectional"))
    )
    (net (code "43") (name "GND") (class "Default")
      (node (ref "C1") (pin "2") (pinfunction "2_2") (pintype "passive"))
      (node (ref "C10") (pin "1") (pinfunction "1_1") (pintype "passive"))
      (node (ref "C11") (pin "1") (pinfunction "1_1") (pintype "passive"))
      (node (ref "C12") (pin "1") (pinfunction "1_1") (pintype "passive"))
      (node (ref "C13") (pin "2") (pinfunction "2_2") (pintype "passive"))
      (node (ref "C14") (pin "2") (pinfunction "2_2") (pintype "passive"))
      (node (ref "C15") (pin "2") (pinfunction "2_2") (pintype "passive"))
      (node (ref "C16") (pin "1") (pinfunction "1_1") (pintype "passive"))
      (node (ref "C17") (pin "2") (pinfunction "2_2") (pintype "passive"))
      (node (ref "C18") (pin "2") (pinfunction "2_2") (pintype "passive"))
      (node (ref "C19") (pin "2") (pinfunction "2_2") (pintype "passive"))
      (node (ref "C2") (pin "2") (pinfunction "2_2") (pintype "passive"))
      (node (ref "C20") (pin "2") (pinfunction "2_2") (pintype "passive"))
      (node (ref "C21") (pin "1") (pinfunction "1_1") (pintype "passive"))
      (node (ref "C22") (pin "2") (pinfunction "2_2") (pintype "passive"))
      (node (ref "C23") (pin "2") (pinfunction "2_2") (pintype "passive"))
      (node (ref "C24") (pin "2") (pinfunction "2_2") (pintype "passive"))
      (node (ref "C25") (pin "2") (pinfunction "2_2") (pintype "passive"))
      (node (ref "C26") (pin "2") (pinfunction "2_2") (pintype "passive"))
      (node (ref "C27") (pin "2") (pinfunction "2_2") (pintype "passive"))
      (node (ref "C28") (pin "2") (pinfunction "2_2") (pintype "passive"))
      (node (ref "C29") (pin "2") (pinfunction "2_2") (pintype "passive"))
      (node (ref "C3") (pin "2") (pinfunction "2_2") (pintype "passive"))
      (node (ref "C30") (pin "2") (pinfunction "2_2") (pintype "passive"))
      (node (ref "C4") (pin "2") (pinfunction "2_2") (pintype "passive"))
      (node (ref "C5") (pin "2") (pinfunction "2_2") (pintype "passive"))
      (node (ref "C6") (pin "2") (pinfunction "2_2") (pintype "passive"))
      (node (ref "C7") (pin "1") (pinfunction "1_1") (pintype "passive"))
      (node (ref "C9") (pin "1") (pinfunction "1_1") (pintype "passive"))
      (node (ref "J1") (pin "4") (pinfunction "4_4") (pintype "passive"))
      (node (ref "J2") (pin "A1B12") (pinfunction "GND_A_A1B12") (pintype "power_in"))
      (node (ref "J2") (pin "B1A12") (pinfunction "GND_B_B1A12") (pintype "power_in"))
      (node (ref "J2") (pin "SH1") (pinfunction "SHIELD_SH1") (pintype "passive"))
      (node (ref "J2") (pin "SH2") (pinfunction "SHIELD_SH2") (pintype "passive"))
      (node (ref "J2") (pin "SH3") (pinfunction "SHIELD_SH3") (pintype "passive"))
      (node (ref "J2") (pin "SH4") (pinfunction "SHIELD_SH4") (pintype "passive"))
      (node (ref "J4") (pin "A1") (pinfunction "A1_A1") (pintype "passive"))
      (node (ref "J5") (pin "C12") (pinfunction "C12_C12") (pintype "passive"))
      (node (ref "J5") (pin "C4") (pinfunction "C4_C4") (pintype "passive"))
      (node (ref "R1") (pin "2") (pinfunction "2_2") (pintype "passive"))
      (node (ref "R11") (pin "2") (pinfunction "2_2") (pintype "passive"))
      (node (ref "R2") (pin "2") (pinfunction "2_2") (pintype "passive"))
      (node (ref "R4") (pin "2") (pinfunction "2_2") (pintype "passive"))
      (node (ref "S1") (pin "2") (pinfunction "2_2") (pintype "passive"))
      (node (ref "S2") (pin "2") (pinfunction "2_2") (pintype "passive"))
      (node (ref "T14") (pin "2") (pinfunction "2_2") (pintype "passive"))
      (node (ref "U1") (pin "2") (pinfunction "2_2") (pintype "passive"))
      (node (ref "U10") (pin "1") (pinfunction "GND_1") (pintype "power_in"))
      (node (ref "U10") (pin "10") (pinfunction "GND_RF_10") (pintype "power_in"))
      (node (ref "U10") (pin "12") (pinfunction "GND_RF_12") (pintype "power_in"))
      (node (ref "U2") (pin "2") (pinfunction "GND_2") (pintype "passive"))
      (node (ref "U3") (pin "33") (pinfunction "GND_33") (pintype "power_in"))
      (node (ref "U4") (pin "2") (pinfunction "NC_2") (pintype "passive"))
      (node (ref "U4") (pin "7") (pinfunction "PS_7") (pintype "input"))
      (node (ref "U5") (pin "B1") (pinfunction "GND_B1") (pintype "power_in"))
      (node (ref "U5") (pin "B2") (pinfunction "ADSEL_B2") (pintype "passive"))
      (node (ref "U5") (pin "C3") (pinfunction "BYPASS_C3") (pintype "power_in"))
      (node (ref "U6") (pin "4") (pinfunction "GND_4") (pintype "power_in"))
      (node (ref "U6") (pin "9") (pinfunction "EXP_9") (pintype "passive"))
      (node (ref "U7") (pin "1") (pinfunction "GND_1") (pintype "power_in"))
      (node (ref "U7") (pin "7") (pinfunction "GND_7") (pintype "power_in"))
      (node (ref "U8") (pin "3") (pinfunction "VSS_3") (pintype "power_in"))
      (node (ref "U8") (pin "8") (pinfunction "VSS_8") (pintype "power_in"))
      (node (ref "U8") (pin "9") (pinfunction "VSS_9") (pintype "power_in"))
      (node (ref "U9") (pin "4") (pinfunction "VSS_4") (pintype "power_in"))
      (node (ref "Y1") (pin "2") (pinfunction "G_2") (pintype "power_in"))
      (node (ref "Y1") (pin "4") (pinfunction "G_4") (pintype "power_in"))
    )
    (net (code "44") (name "Net-(A2-Pad1)") (class "Default")
      (node (ref "A2") (pin "1") (pinfunction "1_1") (pintype "passive"))
      (node (ref "C27") (pin "1") (pinfunction "1_1") (pintype "passive"))
      (node (ref "L4") (pin "1") (pinfunction "1_1") (pintype "passive"))
    )
    (net (code "45") (name "Net-(D1-PadC)") (class "Default")
      (node (ref "D1") (pin "C") (pinfunction "C_C") (pintype "passive"))
      (node (ref "R4") (pin "1") (pinfunction "1_1") (pintype "passive"))
    )
    (net (code "46") (name "Net-(R10-Pad2)") (class "Default")
      (node (ref "R10") (pin "2") (pinfunction "2_2") (pintype "passive"))
      (node (ref "R11") (pin "1") (pinfunction "1_1") (pintype "passive"))
      (node (ref "T13") (pin "2") (pinfunction "2_2") (pintype "passive"))
    )
    (net (code "47") (name "Net-(U2-ADJ{slash}BYP)") (class "Default")
      (node (ref "C4") (pin "1") (pinfunction "1_1") (pintype "passive"))
      (node (ref "U2") (pin "4") (pinfunction "ADJ/BYP_4") (pintype "passive"))
    )
    (net (code "48") (name "Net-(U3-GPIO4{slash}MTMS)") (class "Default")
      (node (ref "T19") (pin "1") (pinfunction "1_1") (pintype "passive"))
      (node (ref "U3") (pin "9") (pinfunction "GPIO4/MTMS_9") (pintype "bidirectional"))
    )
    (net (code "49") (name "Net-(U3-GPIO12{slash}SPIHD)") (class "Default")
      (node (ref "U3") (pin "19") (pinfunction "GPIO12/SPIHD_19") (pintype "bidirectional"))
      (node (ref "U6") (pin "7") (pinfunction "~{HOLD}/~{RESET}/~{IO3}_7") (pintype "bidirectional"))
    )
    (net (code "50") (name "Net-(U3-GPIO13{slash}SPIWP)") (class "Default")
      (node (ref "U3") (pin "20") (pinfunction "GPIO13/SPIWP_20") (pintype "bidirectional"))
      (node (ref "U6") (pin "3") (pinfunction "~{WP}/IO2_3") (pintype "bidirectional"))
    )
    (net (code "51") (name "Net-(U3-GPIO14{slash}SPICS0)") (class "Default")
      (node (ref "U3") (pin "21") (pinfunction "GPIO14/SPICS0_21") (pintype "bidirectional"))
      (node (ref "U6") (pin "1") (pinfunction "~{CS}_1") (pintype "input"))
    )
    (net (code "52") (name "Net-(U3-GPIO15{slash}SPICLK)") (class "Default")
      (node (ref "U3") (pin "22") (pinfunction "GPIO15/SPICLK_22") (pintype "bidirectional"))
      (node (ref "U6") (pin "6") (pinfunction "CLK_6") (pintype "input"))
    )
    (net (code "53") (name "Net-(U3-GPIO16{slash}SPID)") (class "Default")
      (node (ref "U3") (pin "23") (pinfunction "GPIO16/SPID_23") (pintype "bidirectional"))
      (node (ref "U6") (pin "5") (pinfunction "DI/IO0_5") (pintype "bidirectional"))
    )
    (net (code "54") (name "Net-(U3-GPIO17{slash}SPIQ)") (class "Default")
      (node (ref "U3") (pin "24") (pinfunction "GPIO17/SPIQ_24") (pintype "bidirectional"))
      (node (ref "U6") (pin "2") (pinfunction "DO/IO1_2") (pintype "bidirectional"))
    )
    (net (code "55") (name "Net-(U5-CRST)") (class "Default")
      (node (ref "C16") (pin "2") (pinfunction "2_2") (pintype "passive"))
      (node (ref "U5") (pin "C2") (pinfunction "CRST_C2") (pintype "passive"))
    )
    (net (code "56") (name "Net-(U8-SCK)") (class "Default")
      (node (ref "T6") (pin "1") (pinfunction "1_1") (pintype "passive"))
      (node (ref "U8") (pin "2") (pinfunction "SCK_2") (pintype "input"))
    )
    (net (code "57") (name "Net-(U8-SDI)") (class "Default")
      (node (ref "T7") (pin "1") (pinfunction "1_1") (pintype "passive"))
      (node (ref "U8") (pin "4") (pinfunction "SDI_4") (pintype "bidirectional"))
    )
    (net (code "58") (name "Net-(U8-SDO)") (class "Default")
      (node (ref "T8") (pin "1") (pinfunction "1_1") (pintype "passive"))
      (node (ref "U8") (pin "5") (pinfunction "SDO_5") (pintype "bidirectional"))
    )
    (net (code "59") (name "Net-(U9-SCL)") (class "Default")
      (node (ref "T9") (pin "1") (pinfunction "1_1") (pintype "passive"))
      (node (ref "U9") (pin "2") (pinfunction "SCL_2") (pintype "input"))
    )
    (net (code "60") (name "Net-(U9-SDA)") (class "Default")
      (node (ref "T10") (pin "1") (pinfunction "1_1") (pintype "passive"))
      (node (ref "U9") (pin "1") (pinfunction "SDA_1") (pintype "bidirectional"))
    )
    (net (code "61") (name "Net-(U10-I2C_SCL)") (class "Default")
      (node (ref "T15") (pin "1") (pinfunction "1_1") (pintype "passive"))
      (node (ref "U10") (pin "17") (pinfunction "I2C_SCL_17") (pintype "bidirectional"))
    )
    (net (code "62") (name "Net-(U10-I2C_SDA)") (class "Default")
      (node (ref "T16") (pin "1") (pinfunction "1_1") (pintype "passive"))
      (node (ref "U10") (pin "16") (pinfunction "I2C_SDA_16") (pintype "bidirectional"))
    )
    (net (code "63") (name "Net-(U10-PRG)") (class "Default")
      (node (ref "T14") (pin "1") (pinfunction "1_1") (pintype "passive"))
      (node (ref "U10") (pin "18") (pinfunction "PRG_18") (pintype "input"))
    )
    (net (code "64") (name "Net-(U10-UART-RX)") (class "Default")
      (node (ref "J4") (pin "B1") (pinfunction "B1_B1") (pintype "passive"))
      (node (ref "U10") (pin "3") (pinfunction "UART-RX_3") (pintype "input"))
    )
    (net (code "65") (name "Net-(U10-UART-TX)") (class "Default")
      (node (ref "J4") (pin "B2") (pinfunction "B2_B2") (pintype "passive"))
      (node (ref "U10") (pin "2") (pinfunction "UART-TX_2") (pintype "output"))
    )
    (net (code "66") (name "Net-(U10-VBAT)") (class "Default")
      (node (ref "T13") (pin "1") (pinfunction "1_1") (pintype "passive"))
      (node (ref "U10") (pin "6") (pinfunction "VBAT_6") (pintype "power_in"))
    )
    (net (code "67") (name "Net-(U10-WAKEUP)") (class "Default")
      (node (ref "J4") (pin "B3") (pinfunction "B3_B3") (pintype "passive"))
      (node (ref "U10") (pin "5") (pinfunction "WAKEUP_5") (pintype "input"))
    )
    (net (code "68") (name "Net-(U10-~{RESET})") (class "Default")
      (node (ref "T12") (pin "1") (pinfunction "1_1") (pintype "passive"))
      (node (ref "U10") (pin "9") (pinfunction "~{RESET}_9") (pintype "input"))
    )
    (net (code "69") (name "VBUS_FILTER") (class "Default")
      (node (ref "C2") (pin "1") (pinfunction "1_1") (pintype "passive"))
      (node (ref "C3") (pin "1") (pinfunction "1_1") (pintype "passive"))
      (node (ref "L2") (pin "1") (pinfunction "1_1") (pintype "passive"))
      (node (ref "U2") (pin "1") (pinfunction "VIN_1") (pintype "power_in"))
      (node (ref "U2") (pin "3") (pinfunction "EN_3") (pintype "input"))
    )
    (net (code "70") (name "VCC_5VMECHA") (class "Default")
      (node (ref "J1") (pin "1") (pinfunction "1_1") (pintype "passive"))
      (node (ref "J5") (pin "C1") (pinfunction "C1_C1") (pintype "passive"))
    )
    (net (code "71") (name "VCC_VBUS") (class "Default")
      (node (ref "C1") (pin "1") (pinfunction "1_1") (pintype "passive"))
      (node (ref "J2") (pin "A4B9") (pinfunction "VBUS_A_A4B9") (pintype "power_in"))
      (node (ref "J2") (pin "B4A9") (pinfunction "VBUS_B_B4A9") (pintype "power_in"))
      (node (ref "L2") (pin "2") (pinfunction "2_2") (pintype "passive"))
      (node (ref "U1") (pin "5") (pinfunction "5_5") (pintype "passive"))
    )
    (net (code "72") (name "unconnected-(J1-Pad11)") (class "Default")
      (node (ref "J1") (pin "11") (pinfunction "11_11") (pintype "passive"))
    )
    (net (code "73") (name "unconnected-(J1-Pad12)") (class "Default")
      (node (ref "J1") (pin "12") (pinfunction "12_12") (pintype "passive"))
    )
    (net (code "74") (name "unconnected-(J1-Pad13)") (class "Default")
      (node (ref "J1") (pin "13") (pinfunction "13_13") (pintype "passive"))
    )
    (net (code "75") (name "unconnected-(J1-Pad14)") (class "Default")
      (node (ref "J1") (pin "14") (pinfunction "14_14") (pintype "passive"))
    )
    (net (code "76") (name "unconnected-(J1-Pad15)") (class "Default")
      (node (ref "J1") (pin "15") (pinfunction "15_15") (pintype "passive"))
    )
    (net (code "77") (name "unconnected-(J1-Pad16)") (class "Default")
      (node (ref "J1") (pin "16") (pinfunction "16_16") (pintype "passive"))
    )
    (net (code "78") (name "unconnected-(J1-Pad17)") (class "Default")
      (node (ref "J1") (pin "17") (pinfunction "17_17") (pintype "passive"))
    )
    (net (code "79") (name "unconnected-(J1-Pad18)") (class "Default")
      (node (ref "J1") (pin "18") (pinfunction "18_18") (pintype "passive"))
    )
    (net (code "80") (name "unconnected-(J1-Pad19)") (class "Default")
      (node (ref "J1") (pin "19") (pinfunction "19_19") (pintype "passive"))
    )
    (net (code "81") (name "unconnected-(J1-Pad20)") (class "Default")
      (node (ref "J1") (pin "20") (pinfunction "20_20") (pintype "passive"))
    )
    (net (code "82") (name "unconnected-(J2-SBU1-PadA8)") (class "Default")
      (node (ref "J2") (pin "A8") (pinfunction "SBU1_A8") (pintype "bidirectional"))
    )
    (net (code "83") (name "unconnected-(J2-SBU2-PadB8)") (class "Default")
      (node (ref "J2") (pin "B8") (pinfunction "SBU2_B8") (pintype "bidirectional"))
    )
    (net (code "84") (name "unconnected-(J3-Pad1)") (class "Default")
      (node (ref "J3") (pin "1") (pinfunction "1_1") (pintype "passive+no_connect"))
    )
    (net (code "85") (name "unconnected-(J3-Pad2)") (class "Default")
      (node (ref "J3") (pin "2") (pinfunction "2_2") (pintype "passive+no_connect"))
    )
    (net (code "86") (name "unconnected-(J3-Pad3)") (class "Default")
      (node (ref "J3") (pin "3") (pinfunction "3_3") (pintype "passive+no_connect"))
    )
    (net (code "87") (name "unconnected-(J3-Pad4)") (class "Default")
      (node (ref "J3") (pin "4") (pinfunction "4_4") (pintype "passive+no_connect"))
    )
    (net (code "88") (name "unconnected-(J3-Pad5)") (class "Default")
      (node (ref "J3") (pin "5") (pinfunction "5_5") (pintype "passive+no_connect"))
    )
    (net (code "89") (name "unconnected-(J3-Pad6)") (class "Default")
      (node (ref "J3") (pin "6") (pinfunction "6_6") (pintype "passive+no_connect"))
    )
    (net (code "90") (name "unconnected-(J3-Pad7)") (class "Default")
      (node (ref "J3") (pin "7") (pinfunction "7_7") (pintype "passive+no_connect"))
    )
    (net (code "91") (name "unconnected-(J3-Pad10)") (class "Default")
      (node (ref "J3") (pin "10") (pinfunction "10_10") (pintype "passive+no_connect"))
    )
    (net (code "92") (name "unconnected-(J3-Pad11)") (class "Default")
      (node (ref "J3") (pin "11") (pinfunction "11_11") (pintype "passive+no_connect"))
    )
    (net (code "93") (name "unconnected-(J3-Pad12)") (class "Default")
      (node (ref "J3") (pin "12") (pinfunction "12_12") (pintype "passive+no_connect"))
    )
    (net (code "94") (name "unconnected-(J3-Pad13)") (class "Default")
      (node (ref "J3") (pin "13") (pinfunction "13_13") (pintype "passive+no_connect"))
    )
    (net (code "95") (name "unconnected-(J3-Pad14)") (class "Default")
      (node (ref "J3") (pin "14") (pinfunction "14_14") (pintype "passive+no_connect"))
    )
    (net (code "96") (name "unconnected-(J3-Pad15)") (class "Default")
      (node (ref "J3") (pin "15") (pinfunction "15_15") (pintype "passive+no_connect"))
    )
    (net (code "97") (name "unconnected-(J3-Pad16)") (class "Default")
      (node (ref "J3") (pin "16") (pinfunction "16_16") (pintype "passive+no_connect"))
    )
    (net (code "98") (name "unconnected-(J3-Pad17)") (class "Default")
      (node (ref "J3") (pin "17") (pinfunction "17_17") (pintype "passive+no_connect"))
    )
    (net (code "99") (name "unconnected-(J3-Pad18)") (class "Default")
      (node (ref "J3") (pin "18") (pinfunction "18_18") (pintype "passive+no_connect"))
    )
    (net (code "100") (name "unconnected-(J3-Pad19)") (class "Default")
      (node (ref "J3") (pin "19") (pinfunction "19_19") (pintype "passive+no_connect"))
    )
    (net (code "101") (name "unconnected-(J3-Pad20)") (class "Default")
      (node (ref "J3") (pin "20") (pinfunction "20_20") (pintype "passive+no_connect"))
    )
    (net (code "102") (name "unconnected-(J5-PadB1)") (class "Default")
      (node (ref "J5") (pin "B1") (pinfunction "B1_B1") (pintype "passive"))
    )
    (net (code "103") (name "unconnected-(J5-PadB2)") (class "Default")
      (node (ref "J5") (pin "B2") (pinfunction "B2_B2") (pintype "passive"))
    )
    (net (code "104") (name "unconnected-(J5-PadB3)") (class "Default")
      (node (ref "J5") (pin "B3") (pinfunction "B3_B3") (pintype "passive"))
    )
    (net (code "105") (name "unconnected-(J5-PadB4)") (class "Default")
      (node (ref "J5") (pin "B4") (pinfunction "B4_B4") (pintype "passive"))
    )
    (net (code "106") (name "unconnected-(J5-PadB5)") (class "Default")
      (node (ref "J5") (pin "B5") (pinfunction "B5_B5") (pintype "passive"))
    )
    (net (code "107") (name "unconnected-(J5-PadB6)") (class "Default")
      (node (ref "J5") (pin "B6") (pinfunction "B6_B6") (pintype "passive"))
    )
    (net (code "108") (name "unconnected-(J5-PadB7)") (class "Default")
      (node (ref "J5") (pin "B7") (pinfunction "B7_B7") (pintype "passive"))
    )
    (net (code "109") (name "unconnected-(J5-PadB8)") (class "Default")
      (node (ref "J5") (pin "B8") (pinfunction "B8_B8") (pintype "passive"))
    )
    (net (code "110") (name "unconnected-(J5-PadB9)") (class "Default")
      (node (ref "J5") (pin "B9") (pinfunction "B9_B9") (pintype "passive"))
    )
    (net (code "111") (name "unconnected-(J5-PadB10)") (class "Default")
      (node (ref "J5") (pin "B10") (pinfunction "B10_B10") (pintype "passive"))
    )
    (net (code "112") (name "unconnected-(J5-PadB11)") (class "Default")
      (node (ref "J5") (pin "B11") (pinfunction "B11_B11") (pintype "passive"))
    )
    (net (code "113") (name "unconnected-(J5-PadB12)") (class "Default")
      (node (ref "J5") (pin "B12") (pinfunction "B12_B12") (pintype "passive"))
    )
    (net (code "114") (name "unconnected-(J5-PadB13)") (class "Default")
      (node (ref "J5") (pin "B13") (pinfunction "B13_B13") (pintype "passive"))
    )
    (net (code "115") (name "unconnected-(J5-PadB14)") (class "Default")
      (node (ref "J5") (pin "B14") (pinfunction "B14_B14") (pintype "passive"))
    )
    (net (code "116") (name "unconnected-(J5-PadB15)") (class "Default")
      (node (ref "J5") (pin "B15") (pinfunction "B15_B15") (pintype "passive"))
    )
    (net (code "117") (name "unconnected-(J5-PadB16)") (class "Default")
      (node (ref "J5") (pin "B16") (pinfunction "B16_B16") (pintype "passive"))
    )
    (net (code "118") (name "unconnected-(J5-PadB17)") (class "Default")
      (node (ref "J5") (pin "B17") (pinfunction "B17_B17") (pintype "passive"))
    )
    (net (code "119") (name "unconnected-(J5-PadB18)") (class "Default")
      (node (ref "J5") (pin "B18") (pinfunction "B18_B18") (pintype "passive"))
    )
    (net (code "120") (name "unconnected-(J5-PadB19)") (class "Default")
      (node (ref "J5") (pin "B19") (pinfunction "B19_B19") (pintype "passive"))
    )
    (net (code "121") (name "unconnected-(J5-PadB20)") (class "Default")
      (node (ref "J5") (pin "B20") (pinfunction "B20_B20") (pintype "passive"))
    )
    (net (code "122") (name "unconnected-(J5-PadC15)") (class "Default")
      (node (ref "J5") (pin "C15") (pinfunction "C15_C15") (pintype "passive"))
    )
    (net (code "123") (name "unconnected-(J5-PadC16)") (class "Default")
      (node (ref "J5") (pin "C16") (pinfunction "C16_C16") (pintype "passive"))
    )
    (net (code "124") (name "unconnected-(J5-PadC17)") (class "Default")
      (node (ref "J5") (pin "C17") (pinfunction "C17_C17") (pintype "passive"))
    )
    (net (code "125") (name "unconnected-(J5-PadC18)") (class "Default")
      (node (ref "J5") (pin "C18") (pinfunction "C18_C18") (pintype "passive"))
    )
    (net (code "126") (name "unconnected-(J5-PadC19)") (class "Default")
      (node (ref "J5") (pin "C19") (pinfunction "C19_C19") (pintype "passive"))
    )
    (net (code "127") (name "unconnected-(J5-PadC20)") (class "Default")
      (node (ref "J5") (pin "C20") (pinfunction "C20_C20") (pintype "passive"))
    )
    (net (code "128") (name "unconnected-(T15-Pad2)") (class "Default")
      (node (ref "T15") (pin "2") (pinfunction "2_2") (pintype "passive"))
    )
    (net (code "129") (name "unconnected-(T16-Pad2)") (class "Default")
      (node (ref "T16") (pin "2") (pinfunction "2_2") (pintype "passive"))
    )
    (net (code "130") (name "unconnected-(U4-GNDA-Pad4)") (class "Default")
      (node (ref "U4") (pin "4") (pinfunction "GNDA_4") (pintype "power_in"))
    )
    (net (code "131") (name "unconnected-(U4-GNDIO-Pad6)") (class "Default")
      (node (ref "U4") (pin "6") (pinfunction "GNDIO_6") (pintype "power_in"))
    )
    (net (code "132") (name "unconnected-(U4-INT2-Pad1)") (class "Default")
      (node (ref "U4") (pin "1") (pinfunction "INT2_1") (pintype "bidirectional"))
    )
    (net (code "133") (name "unconnected-(U4-INT4-Pad13)") (class "Default")
      (node (ref "U4") (pin "13") (pinfunction "INT4_13") (pintype "bidirectional"))
    )
    (net (code "134") (name "unconnected-(U10-PPS-Pad4)") (class "Default")
      (node (ref "U10") (pin "4") (pinfunction "PPS_4") (pintype "output+no_connect"))
    )
    (net (code "135") (name "unconnected-(U10-RESERVED-Pad7)") (class "Default")
      (node (ref "U10") (pin "7") (pinfunction "RESERVED_7") (pintype "passive+no_connect"))
    )
    (net (code "136") (name "unconnected-(U10-RESERVED-Pad13)") (class "Default")
      (node (ref "U10") (pin "13") (pinfunction "RESERVED_13") (pintype "passive+no_connect"))
    )
    (net (code "137") (name "unconnected-(U10-RESERVED-Pad15)") (class "Default")
      (node (ref "U10") (pin "15") (pinfunction "RESERVED_15") (pintype "passive+no_connect"))
    )
  )
)
